# Sheet4.net
KiCad netlist of a schematic drawn in Altium Designer
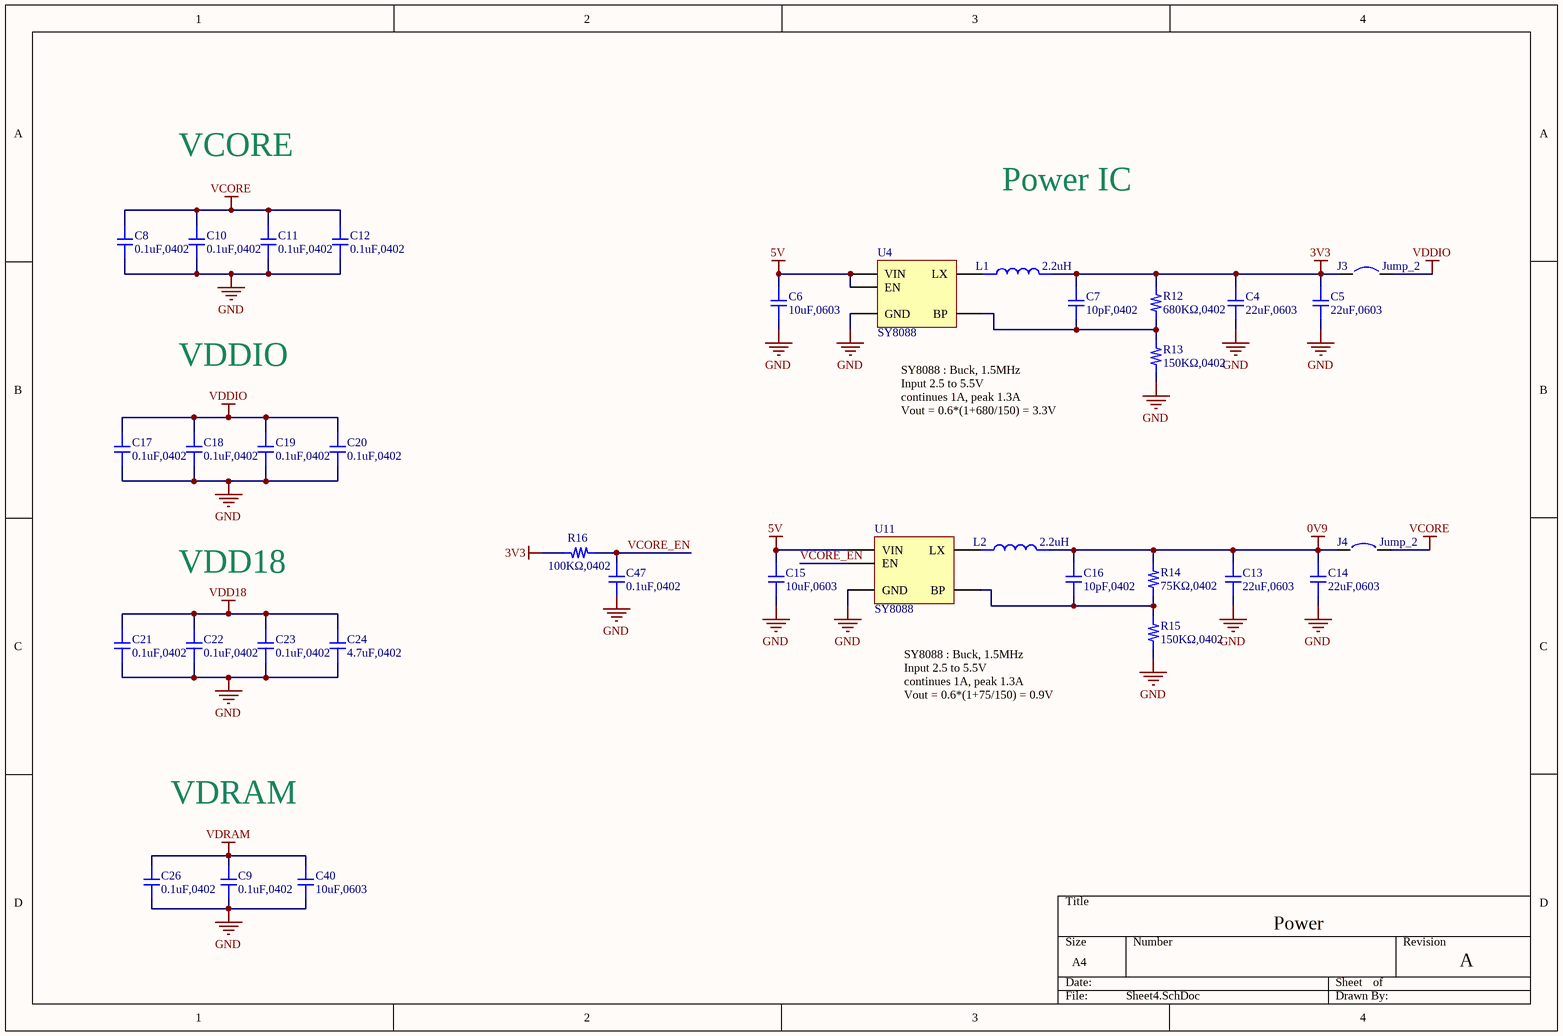
[diagram p0: Sheet4.SchDoc]

(export (version "E")
  (design (tool "Eeschema 10.0.6"))
  (components
    (comp (ref "C4") (value "22uF,0603") (footprint "C0603") (libsource (lib "myLib1") (part "Cap")))
    (comp (ref "C5") (value "22uF,0603") (footprint "C0603") (libsource (lib "myLib1") (part "Cap")))
    (comp (ref "C6") (value "10uF,0603") (footprint "C0603") (libsource (lib "myLib1") (part "Cap")))
    (comp (ref "C7") (value "10pF,0402") (footprint "C0402") (libsource (lib "myLib1") (part "Cap")))
    (comp (ref "C8") (value "0.1uF,0402") (footprint "C0402") (libsource (lib "myLib1") (part "Cap")))
    (comp (ref "C9") (value "0.1uF,0402") (footprint "C0402") (libsource (lib "myLib1") (part "Cap")))
    (comp (ref "C10") (value "0.1uF,0402") (footprint "C0402") (libsource (lib "myLib1") (part "Cap")))
    (comp (ref "C11") (value "0.1uF,0402") (footprint "C0402") (libsource (lib "myLib1") (part "Cap")))
    (comp (ref "C12") (value "0.1uF,0402") (footprint "C0402") (libsource (lib "myLib1") (part "Cap")))
    (comp (ref "C13") (value "22uF,0603") (footprint "C0603") (libsource (lib "myLib1") (part "Cap")))
    (comp (ref "C14") (value "22uF,0603") (footprint "C0603") (libsource (lib "myLib1") (part "Cap")))
    (comp (ref "C15") (value "10uF,0603") (footprint "C0603") (libsource (lib "myLib1") (part "Cap")))
    (comp (ref "C16") (value "10pF,0402") (footprint "C0402") (libsource (lib "myLib1") (part "Cap")))
    (comp (ref "C17") (value "0.1uF,0402") (footprint "C0402") (libsource (lib "myLib1") (part "Cap")))
    (comp (ref "C18") (value "0.1uF,0402") (footprint "C0402") (libsource (lib "myLib1") (part "Cap")))
    (comp (ref "C19") (value "0.1uF,0402") (footprint "C0402") (libsource (lib "myLib1") (part "Cap")))
    (comp (ref "C20") (value "0.1uF,0402") (footprint "C0402") (libsource (lib "myLib1") (part "Cap")))
    (comp (ref "C21") (value "0.1uF,0402") (footprint "C0402") (libsource (lib "myLib1") (part "Cap")))
    (comp (ref "C22") (value "0.1uF,0402") (footprint "C0402") (libsource (lib "myLib1") (part "Cap")))
    (comp (ref "C23") (value "0.1uF,0402") (footprint "C0402") (libsource (lib "myLib1") (part "Cap")))
    (comp (ref "C24") (value "4.7uF,0402") (footprint "C0402") (libsource (lib "myLib1") (part "Cap")))
    (comp (ref "C26") (value "0.1uF,0402") (footprint "C0402") (libsource (lib "myLib1") (part "Cap")))
    (comp (ref "C40") (value "10uF,0603") (footprint "C0603") (libsource (lib "myLib1") (part "Cap")))
    (comp (ref "C47") (value "0.1uF,0402") (footprint "C0402") (libsource (lib "myLib1") (part "Cap")))
    (comp (ref "J3") (value "Jump_2") (footprint "Jp0603") (libsource (lib "myLib1") (part "Jump_2")))
    (comp (ref "J4") (value "Jump_2") (footprint "Jp0603") (libsource (lib "myLib1") (part "Jump_2")))
    (comp (ref "L1") (value "2.2uH") (footprint "IND_252010_SMD") (libsource (lib "myLib1") (part "Ind")))
    (comp (ref "L2") (value "2.2uH") (footprint "IND_252010_SMD") (libsource (lib "myLib1") (part "Ind")))
    (comp (ref "R12") (value "680KΩ,0402") (footprint "R0402") (libsource (lib "myLib1") (part "Res")))
    (comp (ref "R13") (value "150KΩ,0402") (footprint "R0402") (libsource (lib "myLib1") (part "Res")))
    (comp (ref "R14") (value "75KΩ,0402") (footprint "R0402") (libsource (lib "myLib1") (part "Res")))
    (comp (ref "R15") (value "150KΩ,0402") (footprint "R0402") (libsource (lib "myLib1") (part "Res")))
    (comp (ref "R16") (value "100KΩ,0402") (footprint "R0402") (libsource (lib "myLib1") (part "Res")))
    (comp (ref "U4") (value "SY8088") (footprint "SOT-23-5p") (libsource (lib "myLib1") (part "SY8088")))
    (comp (ref "U11") (value "SY8088") (footprint "SOT-23-5p") (libsource (lib "myLib1") (part "SY8088")))
  )
  (nets
    (net (code "1") (name "/VCORE_EN") (class "Default")
      (node (ref "C47") (pin "02") (pintype "passive"))
      (node (ref "R16") (pin "01") (pintype "passive"))
      (node (ref "U11") (pin "01") (pinfunction "EN_01") (pintype "passive"))
    )
    (net (code "2") (name "0V9") (class "Default")
      (node (ref "C13") (pin "02") (pintype "passive"))
      (node (ref "C14") (pin "02") (pintype "passive"))
      (node (ref "C16") (pin "01") (pintype "passive"))
      (node (ref "J4") (pin "01") (pinfunction "1_01") (pintype "passive"))
      (node (ref "L2") (pin "02") (pinfunction "02_02") (pintype "passive"))
      (node (ref "R14") (pin "01") (pintype "passive"))
    )
    (net (code "3") (name "3V3") (class "Default")
      (node (ref "C4") (pin "02") (pintype "passive"))
      (node (ref "C5") (pin "02") (pintype "passive"))
      (node (ref "C7") (pin "01") (pintype "passive"))
      (node (ref "J3") (pin "01") (pinfunction "1_01") (pintype "passive"))
      (node (ref "L1") (pin "02") (pinfunction "02_02") (pintype "passive"))
      (node (ref "R12") (pin "01") (pintype "passive"))
      (node (ref "R16") (pin "02") (pintype "passive"))
    )
    (net (code "4") (name "5V") (class "Default")
      (node (ref "C15") (pin "01") (pintype "passive"))
      (node (ref "C6") (pin "01") (pintype "passive"))
      (node (ref "U11") (pin "04") (pinfunction "VIN_04") (pintype "passive"))
      (node (ref "U4") (pin "01") (pinfunction "EN_01") (pintype "passive"))
      (node (ref "U4") (pin "04") (pinfunction "VIN_04") (pintype "passive"))
    )
    (net (code "5") (name "GND") (class "Default")
      (node (ref "C10") (pin "01") (pintype "passive"))
      (node (ref "C11") (pin "01") (pintype "passive"))
      (node (ref "C12") (pin "01") (pintype "passive"))
      (node (ref "C13") (pin "01") (pintype "passive"))
      (node (ref "C14") (pin "01") (pintype "passive"))
      (node (ref "C15") (pin "02") (pintype "passive"))
      (node (ref "C17") (pin "01") (pintype "passive"))
      (node (ref "C18") (pin "01") (pintype "passive"))
      (node (ref "C19") (pin "01") (pintype "passive"))
      (node (ref "C20") (pin "01") (pintype "passive"))
      (node (ref "C21") (pin "01") (pintype "passive"))
      (node (ref "C22") (pin "01") (pintype "passive"))
      (node (ref "C23") (pin "01") (pintype "passive"))
      (node (ref "C24") (pin "01") (pintype "passive"))
      (node (ref "C26") (pin "01") (pintype "passive"))
      (node (ref "C4") (pin "01") (pintype "passive"))
      (node (ref "C40") (pin "01") (pintype "passive"))
      (node (ref "C47") (pin "01") (pintype "passive"))
      (node (ref "C5") (pin "01") (pintype "passive"))
      (node (ref "C6") (pin "02") (pintype "passive"))
      (node (ref "C8") (pin "01") (pintype "passive"))
      (node (ref "C9") (pin "01") (pintype "passive"))
      (node (ref "R13") (pin "01") (pintype "passive"))
      (node (ref "R15") (pin "01") (pintype "passive"))
      (node (ref "U11") (pin "02") (pinfunction "GND_02") (pintype "passive"))
      (node (ref "U4") (pin "02") (pinfunction "GND_02") (pintype "passive"))
    )
    (net (code "6") (name "Net-(U4-BP)") (class "Default")
      (node (ref "C7") (pin "02") (pintype "passive"))
      (node (ref "R12") (pin "02") (pintype "passive"))
      (node (ref "R13") (pin "02") (pintype "passive"))
      (node (ref "U4") (pin "05") (pinfunction "BP_05") (pintype "passive"))
    )
    (net (code "7") (name "Net-(U4-LX)") (class "Default")
      (node (ref "L1") (pin "01") (pinfunction "01_01") (pintype "passive"))
      (node (ref "U4") (pin "03") (pinfunction "LX_03") (pintype "passive"))
    )
    (net (code "8") (name "Net-(U11-BP)") (class "Default")
      (node (ref "C16") (pin "02") (pintype "passive"))
      (node (ref "R14") (pin "02") (pintype "passive"))
      (node (ref "R15") (pin "02") (pintype "passive"))
      (node (ref "U11") (pin "05") (pinfunction "BP_05") (pintype "passive"))
    )
    (net (code "9") (name "Net-(U11-LX)") (class "Default")
      (node (ref "L2") (pin "01") (pinfunction "01_01") (pintype "passive"))
      (node (ref "U11") (pin "03") (pinfunction "LX_03") (pintype "passive"))
    )
    (net (code "10") (name "VCORE") (class "Default")
      (node (ref "C10") (pin "02") (pintype "passive"))
      (node (ref "C11") (pin "02") (pintype "passive"))
      (node (ref "C12") (pin "02") (pintype "passive"))
      (node (ref "C8") (pin "02") (pintype "passive"))
      (node (ref "J4") (pin "02") (pinfunction "2_02") (pintype "passive"))
    )
    (net (code "11") (name "VDD18") (class "Default")
      (node (ref "C21") (pin "02") (pintype "passive"))
      (node (ref "C22") (pin "02") (pintype "passive"))
      (node (ref "C23") (pin "02") (pintype "passive"))
      (node (ref "C24") (pin "02") (pintype "passive"))
    )
    (net (code "12") (name "VDDIO") (class "Default")
      (node (ref "C17") (pin "02") (pintype "passive"))
      (node (ref "C18") (pin "02") (pintype "passive"))
      (node (ref "C19") (pin "02") (pintype "passive"))
      (node (ref "C20") (pin "02") (pintype "passive"))
      (node (ref "J3") (pin "02") (pinfunction "2_02") (pintype "passive"))
    )
    (net (code "13") (name "VDRAM") (class "Default")
      (node (ref "C26") (pin "02") (pintype "passive"))
      (node (ref "C40") (pin "02") (pintype "passive"))
      (node (ref "C9") (pin "02") (pintype "passive"))
    )
  )
)
